# Sheet.net
KiCad netlist of a schematic drawn in Altium Designer
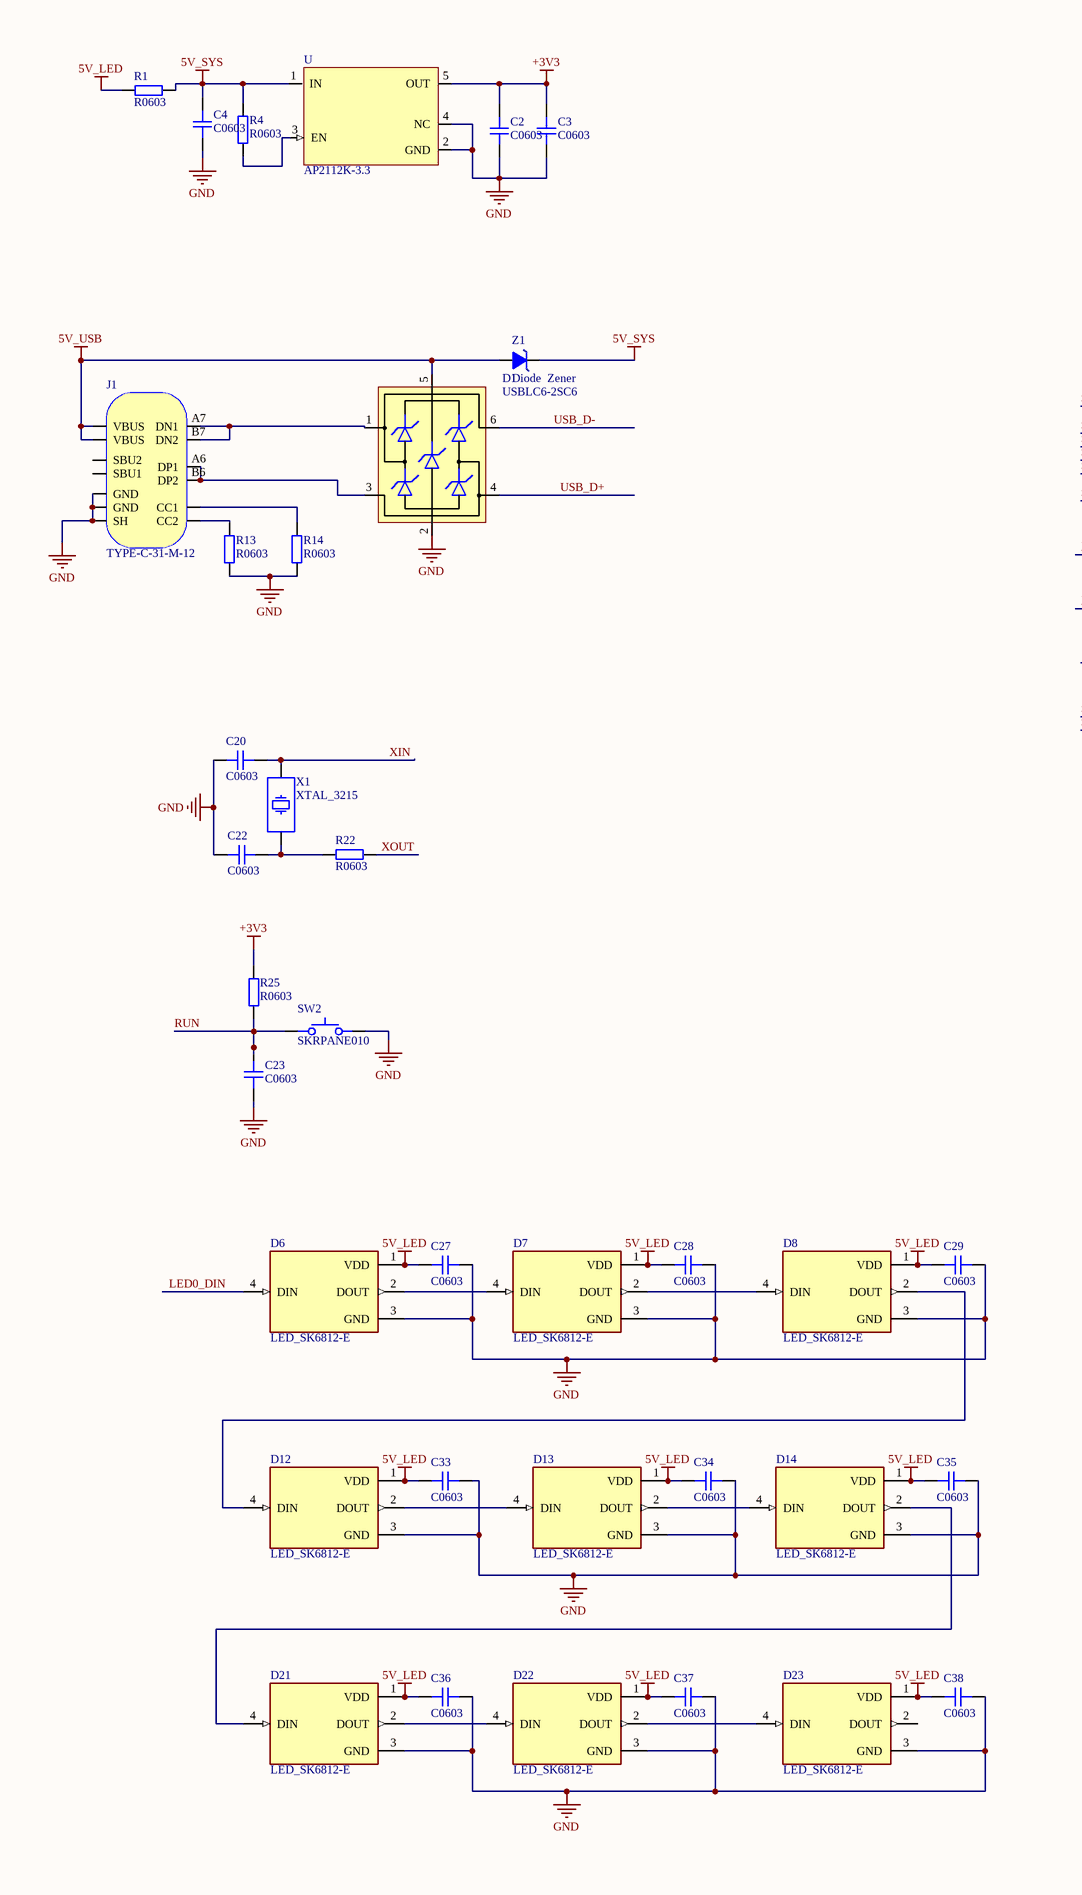
[diagram p0: Sheet.SchDoc, left]
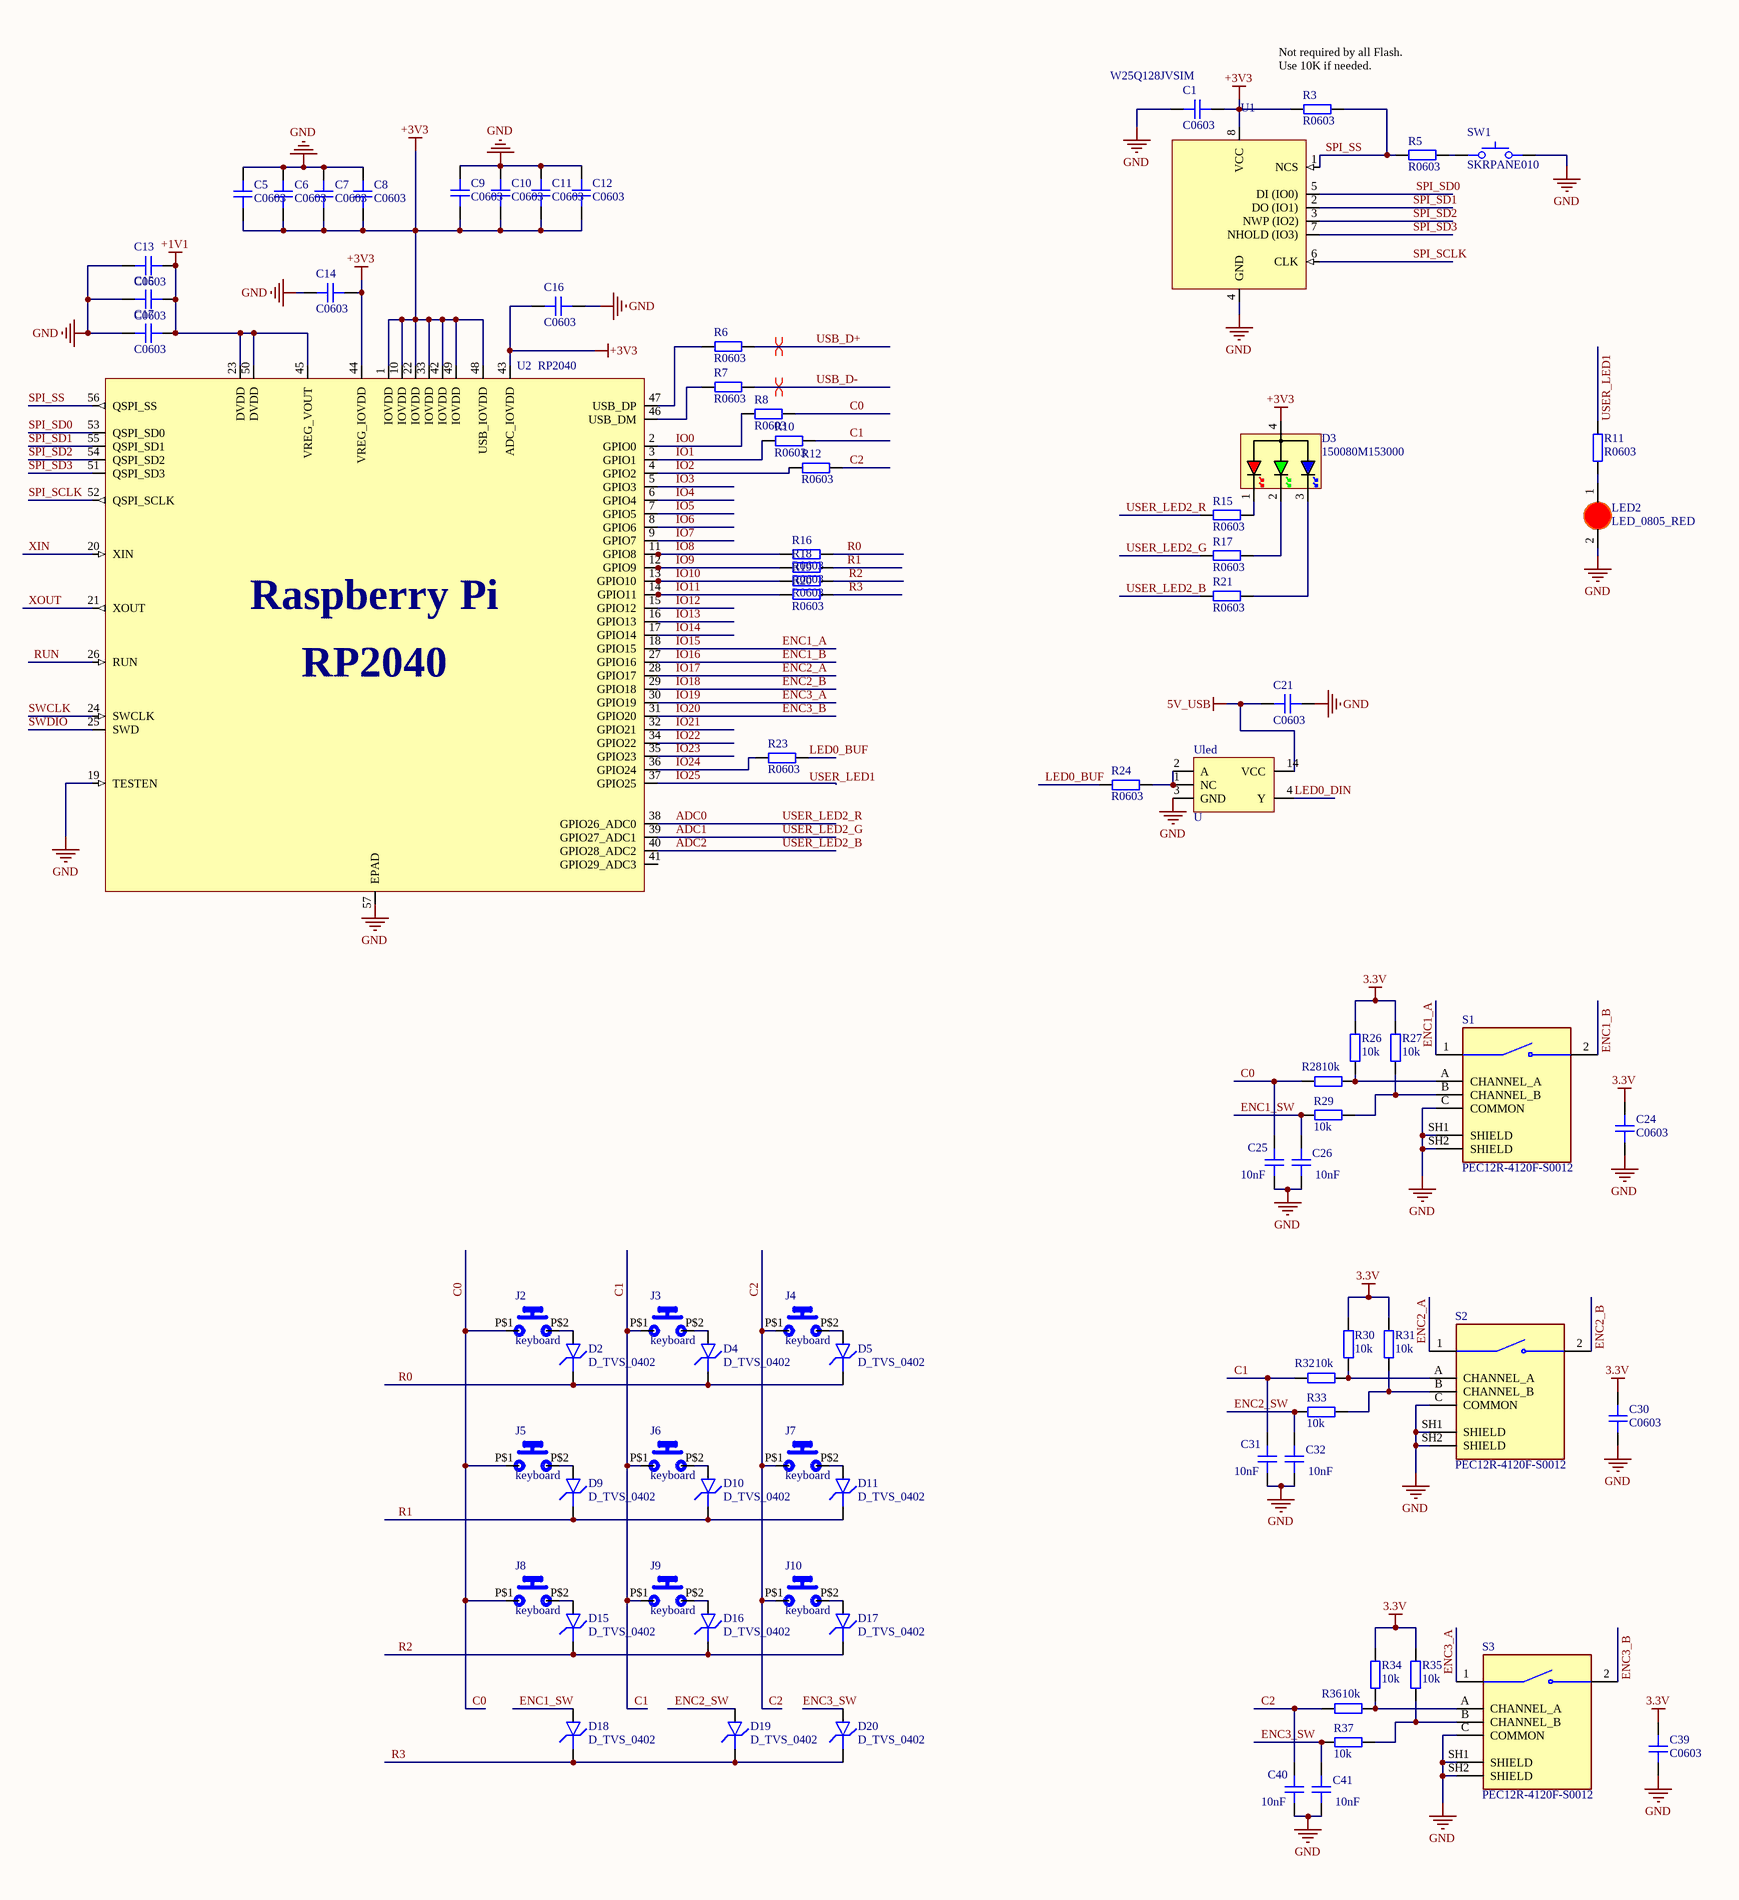
[diagram p1: Sheet.SchDoc, right]

(export (version "E")
  (design (tool "Eeschema 10.0.6"))
  (components
    (comp (ref "C1")
      (value "C0603")
      (footprint "CAP_0603")
      (description "Capacitor SMD 0603")
      (libsource (lib "bethu") (part "CAP_0603"))
    )
    (comp (ref "C2")
      (value "C0603")
      (footprint "CAP_0603")
      (description "Capacitor SMD 0603")
      (libsource (lib "bethu") (part "CAP_0603"))
    )
    (comp (ref "C3")
      (value "C0603")
      (footprint "CAP_0603")
      (description "Capacitor SMD 0603")
      (libsource (lib "bethu") (part "CAP_0603"))
    )
    (comp (ref "C4")
      (value "C0603")
      (footprint "CAP_0603")
      (description "Capacitor SMD 0603")
      (libsource (lib "bethu") (part "CAP_0603"))
    )
    (comp (ref "C5")
      (value "C0603")
      (footprint "CAP_0603")
      (description "Capacitor SMD 0603")
      (libsource (lib "bethu") (part "CAP_0603"))
    )
    (comp (ref "C6")
      (value "C0603")
      (footprint "CAP_0603")
      (description "Capacitor SMD 0603")
      (libsource (lib "bethu") (part "CAP_0603"))
    )
    (comp (ref "C7")
      (value "C0603")
      (footprint "CAP_0603")
      (description "Capacitor SMD 0603")
      (libsource (lib "bethu") (part "CAP_0603"))
    )
    (comp (ref "C8")
      (value "C0603")
      (footprint "CAP_0603")
      (description "Capacitor SMD 0603")
      (libsource (lib "bethu") (part "CAP_0603"))
    )
    (comp (ref "C9")
      (value "C0603")
      (footprint "CAP_0603")
      (description "Capacitor SMD 0603")
      (libsource (lib "bethu") (part "CAP_0603"))
    )
    (comp (ref "C10")
      (value "C0603")
      (footprint "CAP_0603")
      (description "Capacitor SMD 0603")
      (libsource (lib "bethu") (part "CAP_0603"))
    )
    (comp (ref "C11")
      (value "C0603")
      (footprint "CAP_0603")
      (description "Capacitor SMD 0603")
      (libsource (lib "bethu") (part "CAP_0603"))
    )
    (comp (ref "C12")
      (value "C0603")
      (footprint "CAP_0603")
      (description "Capacitor SMD 0603")
      (libsource (lib "bethu") (part "CAP_0603"))
    )
    (comp (ref "C13")
      (value "C0603")
      (footprint "CAP_0603")
      (description "Capacitor SMD 0603")
      (libsource (lib "bethu") (part "CAP_0603"))
    )
    (comp (ref "C14")
      (value "C0603")
      (footprint "CAP_0603")
      (description "Capacitor SMD 0603")
      (libsource (lib "bethu") (part "CAP_0603"))
    )
    (comp (ref "C15")
      (value "C0603")
      (footprint "CAP_0603")
      (description "Capacitor SMD 0603")
      (libsource (lib "bethu") (part "CAP_0603"))
    )
    (comp (ref "C16")
      (value "C0603")
      (footprint "CAP_0603")
      (description "Capacitor SMD 0603")
      (libsource (lib "bethu") (part "CAP_0603"))
    )
    (comp (ref "C17")
      (value "C0603")
      (footprint "CAP_0603")
      (description "Capacitor SMD 0603")
      (libsource (lib "bethu") (part "CAP_0603"))
    )
    (comp (ref "C20")
      (value "C0603")
      (footprint "CAP_0603")
      (description "Capacitor SMD 0603")
      (libsource (lib "bethu") (part "CAP_0603"))
    )
    (comp (ref "C21")
      (value "C0603")
      (footprint "CAP_0603")
      (description "Capacitor SMD 0603")
      (libsource (lib "bethu") (part "CAP_0603"))
    )
    (comp (ref "C22")
      (value "C0603")
      (footprint "CAP_0603")
      (description "Capacitor SMD 0603")
      (libsource (lib "bethu") (part "CAP_0603"))
    )
    (comp (ref "C23")
      (value "C0603")
      (footprint "CAP_0603")
      (description "Capacitor SMD 0603")
      (libsource (lib "bethu") (part "CAP_0603"))
    )
    (comp (ref "C24")
      (value "C0603")
      (footprint "CAP_0603")
      (description "Capacitor SMD 0603")
      (libsource (lib "bethu") (part "CAP_0603"))
    )
    (comp (ref "C25")
      (value "10nF")
      (footprint "CAP_0603")
      (description "Capacitor SMD 0603")
      (libsource (lib "bethu") (part "CAP_0603"))
    )
    (comp (ref "C26")
      (value "10nF")
      (footprint "CAP_0603")
      (description "Capacitor SMD 0603")
      (libsource (lib "bethu") (part "CAP_0603"))
    )
    (comp (ref "C27")
      (value "C0603")
      (footprint "CAP_0603")
      (description "Capacitor SMD 0603")
      (libsource (lib "bethu") (part "CAP_0603"))
    )
    (comp (ref "C28")
      (value "C0603")
      (footprint "CAP_0603")
      (description "Capacitor SMD 0603")
      (libsource (lib "bethu") (part "CAP_0603"))
    )
    (comp (ref "C29")
      (value "C0603")
      (footprint "CAP_0603")
      (description "Capacitor SMD 0603")
      (libsource (lib "bethu") (part "CAP_0603"))
    )
    (comp (ref "C30")
      (value "C0603")
      (footprint "CAP_0603")
      (description "Capacitor SMD 0603")
      (libsource (lib "bethu") (part "CAP_0603"))
    )
    (comp (ref "C31")
      (value "10nF")
      (footprint "CAP_0603")
      (description "Capacitor SMD 0603")
      (libsource (lib "bethu") (part "CAP_0603"))
    )
    (comp (ref "C32")
      (value "10nF")
      (footprint "CAP_0603")
      (description "Capacitor SMD 0603")
      (libsource (lib "bethu") (part "CAP_0603"))
    )
    (comp (ref "C33")
      (value "C0603")
      (footprint "CAP_0603")
      (description "Capacitor SMD 0603")
      (libsource (lib "bethu") (part "CAP_0603"))
    )
    (comp (ref "C34")
      (value "C0603")
      (footprint "CAP_0603")
      (description "Capacitor SMD 0603")
      (libsource (lib "bethu") (part "CAP_0603"))
    )
    (comp (ref "C35")
      (value "C0603")
      (footprint "CAP_0603")
      (description "Capacitor SMD 0603")
      (libsource (lib "bethu") (part "CAP_0603"))
    )
    (comp (ref "C36")
      (value "C0603")
      (footprint "CAP_0603")
      (description "Capacitor SMD 0603")
      (libsource (lib "bethu") (part "CAP_0603"))
    )
    (comp (ref "C37")
      (value "C0603")
      (footprint "CAP_0603")
      (description "Capacitor SMD 0603")
      (libsource (lib "bethu") (part "CAP_0603"))
    )
    (comp (ref "C38")
      (value "C0603")
      (footprint "CAP_0603")
      (description "Capacitor SMD 0603")
      (libsource (lib "bethu") (part "CAP_0603"))
    )
    (comp (ref "C39")
      (value "C0603")
      (footprint "CAP_0603")
      (description "Capacitor SMD 0603")
      (libsource (lib "bethu") (part "CAP_0603"))
    )
    (comp (ref "C40")
      (value "10nF")
      (footprint "CAP_0603")
      (description "Capacitor SMD 0603")
      (libsource (lib "bethu") (part "CAP_0603"))
    )
    (comp (ref "C41")
      (value "10nF")
      (footprint "CAP_0603")
      (description "Capacitor SMD 0603")
      (libsource (lib "bethu") (part "CAP_0603"))
    )
    (comp (ref "D1")
      (value "USBLC6-2SC6")
      (footprint "SOT-23-6")
      (description "Low-Capacitance ESD Protection USB")
      (fields (field (name "MANUFACTURER") "STMicroelectronics"))
      (libsource (lib "bethu") (part "USBLC6-2SC6"))
    )
    (comp (ref "D2")
      (value "D_TVS_0402")
      (footprint "D_0402")
      (description "Diode TVS / ESD 0402")
      (libsource (lib "bethu") (part "D_TVS_0402"))
    )
    (comp (ref "D3")
      (value "150080M153000")
      (footprint "150080M153000")
      (description "RGB LED Common Anode SMD Diffused 0805 Top View")
      (fields (field (name "MANUFACTURER") "Wurth"))
      (libsource (lib "bethu") (part "LED RGB"))
    )
    (comp (ref "D4")
      (value "D_TVS_0402")
      (footprint "D_0402")
      (description "Diode TVS / ESD 0402")
      (libsource (lib "bethu") (part "D_TVS_0402"))
    )
    (comp (ref "D5")
      (value "D_TVS_0402")
      (footprint "D_0402")
      (description "Diode TVS / ESD 0402")
      (libsource (lib "bethu") (part "D_TVS_0402"))
    )
    (comp (ref "D6")
      (value "LED_SK6812-E")
      (footprint "LED_SK6812-E")
      (fields (field (name "MF") "DONGGUANG OPSCO OPTOELECTRONICS CO., LTD") (field (name "MP") "SK6812-E"))
      (libsource (lib "bethu") (part "LED_SK6812-E"))
    )
    (comp (ref "D7")
      (value "LED_SK6812-E")
      (footprint "LED_SK6812-E")
      (fields (field (name "MF") "DONGGUANG OPSCO OPTOELECTRONICS CO., LTD") (field (name "MP") "SK6812-E"))
      (libsource (lib "bethu") (part "LED_SK6812-E"))
    )
    (comp (ref "D8")
      (value "LED_SK6812-E")
      (footprint "LED_SK6812-E")
      (fields (field (name "MF") "DONGGUANG OPSCO OPTOELECTRONICS CO., LTD") (field (name "MP") "SK6812-E"))
      (libsource (lib "bethu") (part "LED_SK6812-E"))
    )
    (comp (ref "D9")
      (value "D_TVS_0402")
      (footprint "D_0402")
      (description "Diode TVS / ESD 0402")
      (libsource (lib "bethu") (part "D_TVS_0402"))
    )
    (comp (ref "D10")
      (value "D_TVS_0402")
      (footprint "D_0402")
      (description "Diode TVS / ESD 0402")
      (libsource (lib "bethu") (part "D_TVS_0402"))
    )
    (comp (ref "D11")
      (value "D_TVS_0402")
      (footprint "D_0402")
      (description "Diode TVS / ESD 0402")
      (libsource (lib "bethu") (part "D_TVS_0402"))
    )
    (comp (ref "D12")
      (value "LED_SK6812-E")
      (footprint "LED_SK6812-E")
      (fields (field (name "MF") "DONGGUANG OPSCO OPTOELECTRONICS CO., LTD") (field (name "MP") "SK6812-E"))
      (libsource (lib "bethu") (part "LED_SK6812-E"))
    )
    (comp (ref "D13")
      (value "LED_SK6812-E")
      (footprint "LED_SK6812-E")
      (fields (field (name "MF") "DONGGUANG OPSCO OPTOELECTRONICS CO., LTD") (field (name "MP") "SK6812-E"))
      (libsource (lib "bethu") (part "LED_SK6812-E"))
    )
    (comp (ref "D14")
      (value "LED_SK6812-E")
      (footprint "LED_SK6812-E")
      (fields (field (name "MF") "DONGGUANG OPSCO OPTOELECTRONICS CO., LTD") (field (name "MP") "SK6812-E"))
      (libsource (lib "bethu") (part "LED_SK6812-E"))
    )
    (comp (ref "D15")
      (value "D_TVS_0402")
      (footprint "D_0402")
      (description "Diode TVS / ESD 0402")
      (libsource (lib "bethu") (part "D_TVS_0402"))
    )
    (comp (ref "D16")
      (value "D_TVS_0402")
      (footprint "D_0402")
      (description "Diode TVS / ESD 0402")
      (libsource (lib "bethu") (part "D_TVS_0402"))
    )
    (comp (ref "D17")
      (value "D_TVS_0402")
      (footprint "D_0402")
      (description "Diode TVS / ESD 0402")
      (libsource (lib "bethu") (part "D_TVS_0402"))
    )
    (comp (ref "D18")
      (value "D_TVS_0402")
      (footprint "D_0402")
      (description "Diode TVS / ESD 0402")
      (libsource (lib "bethu") (part "D_TVS_0402"))
    )
    (comp (ref "D19")
      (value "D_TVS_0402")
      (footprint "D_0402")
      (description "Diode TVS / ESD 0402")
      (libsource (lib "bethu") (part "D_TVS_0402"))
    )
    (comp (ref "D20")
      (value "D_TVS_0402")
      (footprint "D_0402")
      (description "Diode TVS / ESD 0402")
      (libsource (lib "bethu") (part "D_TVS_0402"))
    )
    (comp (ref "D21")
      (value "LED_SK6812-E")
      (footprint "LED_SK6812-E")
      (fields (field (name "MF") "DONGGUANG OPSCO OPTOELECTRONICS CO., LTD") (field (name "MP") "SK6812-E"))
      (libsource (lib "bethu") (part "LED_SK6812-E"))
    )
    (comp (ref "D22")
      (value "LED_SK6812-E")
      (footprint "LED_SK6812-E")
      (fields (field (name "MF") "DONGGUANG OPSCO OPTOELECTRONICS CO., LTD") (field (name "MP") "SK6812-E"))
      (libsource (lib "bethu") (part "LED_SK6812-E"))
    )
    (comp (ref "D23")
      (value "LED_SK6812-E")
      (footprint "LED_SK6812-E")
      (fields (field (name "MF") "DONGGUANG OPSCO OPTOELECTRONICS CO., LTD") (field (name "MP") "SK6812-E"))
      (libsource (lib "bethu") (part "LED_SK6812-E"))
    )
    (comp (ref "J1")
      (value "TYPE-C-31-M-12")
      (footprint "TYPE-C-31-M-12")
      (description "USB Type C Connector Horizontal SMT")
      (fields (field (name "MANUFACTURER") "Koren Hroparts"))
      (libsource (lib "bethu") (part "TYPE-C-31-M-12"))
    )
    (comp (ref "J2")
      (value "keyboard")
      (footprint "SWITCH_keyboard")
      (fields (field (name "MF") "Cherry") (field (name "MP") "MX1A-11NN"))
      (libsource (lib "bethu") (part "keyboard"))
    )
    (comp (ref "J3")
      (value "keyboard")
      (footprint "SWITCH_keyboard")
      (fields (field (name "MF") "Cherry") (field (name "MP") "MX1A-11NN"))
      (libsource (lib "bethu") (part "keyboard"))
    )
    (comp (ref "J4")
      (value "keyboard")
      (footprint "SWITCH_keyboard")
      (fields (field (name "MF") "Cherry") (field (name "MP") "MX1A-11NN"))
      (libsource (lib "bethu") (part "keyboard"))
    )
    (comp (ref "J5")
      (value "keyboard")
      (footprint "SWITCH_keyboard")
      (fields (field (name "MF") "Cherry") (field (name "MP") "MX1A-11NN"))
      (libsource (lib "bethu") (part "keyboard"))
    )
    (comp (ref "J6")
      (value "keyboard")
      (footprint "SWITCH_keyboard")
      (fields (field (name "MF") "Cherry") (field (name "MP") "MX1A-11NN"))
      (libsource (lib "bethu") (part "keyboard"))
    )
    (comp (ref "J7")
      (value "keyboard")
      (footprint "SWITCH_keyboard")
      (fields (field (name "MF") "Cherry") (field (name "MP") "MX1A-11NN"))
      (libsource (lib "bethu") (part "keyboard"))
    )
    (comp (ref "J8")
      (value "keyboard")
      (footprint "SWITCH_keyboard")
      (fields (field (name "MF") "Cherry") (field (name "MP") "MX1A-11NN"))
      (libsource (lib "bethu") (part "keyboard"))
    )
    (comp (ref "J9")
      (value "keyboard")
      (footprint "SWITCH_keyboard")
      (fields (field (name "MF") "Cherry") (field (name "MP") "MX1A-11NN"))
      (libsource (lib "bethu") (part "keyboard"))
    )
    (comp (ref "J10")
      (value "keyboard")
      (footprint "SWITCH_keyboard")
      (fields (field (name "MF") "Cherry") (field (name "MP") "MX1A-11NN"))
      (libsource (lib "bethu") (part "keyboard"))
    )
    (comp (ref "LED2")
      (value "LED_0805_RED")
      (footprint "LED-0805-Red")
      (libsource (lib "bethu") (part "LED_0805_RED"))
    )
    (comp (ref "R1")
      (value "R0603")
      (footprint "RES_0603")
      (description "Resistor SMD 0603")
      (libsource (lib "bethu") (part "RES_0603"))
    )
    (comp (ref "R3")
      (value "R0603")
      (footprint "RES_0603")
      (description "Resistor SMD 0603")
      (libsource (lib "bethu") (part "RES_0603"))
    )
    (comp (ref "R4")
      (value "R0603")
      (footprint "RES_0603")
      (description "Resistor SMD 0603")
      (libsource (lib "bethu") (part "RES_0603"))
    )
    (comp (ref "R5")
      (value "R0603")
      (footprint "RES_0603")
      (description "Resistor SMD 0603")
      (libsource (lib "bethu") (part "RES_0603"))
    )
    (comp (ref "R6")
      (value "R0603")
      (footprint "RES_0603")
      (description "Resistor SMD 0603")
      (libsource (lib "bethu") (part "RES_0603"))
    )
    (comp (ref "R7")
      (value "R0603")
      (footprint "RES_0603")
      (description "Resistor SMD 0603")
      (libsource (lib "bethu") (part "RES_0603"))
    )
    (comp (ref "R8")
      (value "R0603")
      (footprint "RES_0603")
      (description "Resistor SMD 0603")
      (libsource (lib "bethu") (part "RES_0603"))
    )
    (comp (ref "R10")
      (value "R0603")
      (footprint "RES_0603")
      (description "Resistor SMD 0603")
      (libsource (lib "bethu") (part "RES_0603"))
    )
    (comp (ref "R11")
      (value "R0603")
      (footprint "RES_0603")
      (description "Resistor SMD 0603")
      (libsource (lib "bethu") (part "RES_0603"))
    )
    (comp (ref "R12")
      (value "R0603")
      (footprint "RES_0603")
      (description "Resistor SMD 0603")
      (libsource (lib "bethu") (part "RES_0603"))
    )
    (comp (ref "R13")
      (value "R0603")
      (footprint "RES_0603")
      (description "Resistor SMD 0603")
      (libsource (lib "bethu") (part "RES_0603"))
    )
    (comp (ref "R14")
      (value "R0603")
      (footprint "RES_0603")
      (description "Resistor SMD 0603")
      (libsource (lib "bethu") (part "RES_0603"))
    )
    (comp (ref "R15")
      (value "R0603")
      (footprint "RES_0603")
      (description "Resistor SMD 0603")
      (libsource (lib "bethu") (part "RES_0603"))
    )
    (comp (ref "R16")
      (value "R0603")
      (footprint "RES_0603")
      (description "Resistor SMD 0603")
      (libsource (lib "bethu") (part "RES_0603"))
    )
    (comp (ref "R17")
      (value "R0603")
      (footprint "RES_0603")
      (description "Resistor SMD 0603")
      (libsource (lib "bethu") (part "RES_0603"))
    )
    (comp (ref "R18")
      (value "R0603")
      (footprint "RES_0603")
      (description "Resistor SMD 0603")
      (libsource (lib "bethu") (part "RES_0603"))
    )
    (comp (ref "R19")
      (value "R0603")
      (footprint "RES_0603")
      (description "Resistor SMD 0603")
      (libsource (lib "bethu") (part "RES_0603"))
    )
    (comp (ref "R20")
      (value "R0603")
      (footprint "RES_0603")
      (description "Resistor SMD 0603")
      (libsource (lib "bethu") (part "RES_0603"))
    )
    (comp (ref "R21")
      (value "R0603")
      (footprint "RES_0603")
      (description "Resistor SMD 0603")
      (libsource (lib "bethu") (part "RES_0603"))
    )
    (comp (ref "R22")
      (value "R0603")
      (footprint "RES_0603")
      (description "Resistor SMD 0603")
      (libsource (lib "bethu") (part "RES_0603"))
    )
    (comp (ref "R23")
      (value "R0603")
      (footprint "RES_0603")
      (description "Resistor SMD 0603")
      (libsource (lib "bethu") (part "RES_0603"))
    )
    (comp (ref "R24")
      (value "R0603")
      (footprint "RES_0603")
      (description "Resistor SMD 0603")
      (libsource (lib "bethu") (part "RES_0603"))
    )
    (comp (ref "R25")
      (value "R0603")
      (footprint "RES_0603")
      (description "Resistor SMD 0603")
      (libsource (lib "bethu") (part "RES_0603"))
    )
    (comp (ref "R26")
      (value "10k")
      (footprint "RES_0603")
      (description "Resistor SMD 0603")
      (libsource (lib "bethu") (part "RES_0603"))
    )
    (comp (ref "R27")
      (value "10k")
      (footprint "RES_0603")
      (description "Resistor SMD 0603")
      (libsource (lib "bethu") (part "RES_0603"))
    )
    (comp (ref "R28")
      (value "10k")
      (footprint "RES_0603")
      (description "Resistor SMD 0603")
      (libsource (lib "bethu") (part "RES_0603"))
    )
    (comp (ref "R29")
      (value "10k")
      (footprint "RES_0603")
      (description "Resistor SMD 0603")
      (libsource (lib "bethu") (part "RES_0603"))
    )
    (comp (ref "R30")
      (value "10k")
      (footprint "RES_0603")
      (description "Resistor SMD 0603")
      (libsource (lib "bethu") (part "RES_0603"))
    )
    (comp (ref "R31")
      (value "10k")
      (footprint "RES_0603")
      (description "Resistor SMD 0603")
      (libsource (lib "bethu") (part "RES_0603"))
    )
    (comp (ref "R32")
      (value "10k")
      (footprint "RES_0603")
      (description "Resistor SMD 0603")
      (libsource (lib "bethu") (part "RES_0603"))
    )
    (comp (ref "R33")
      (value "10k")
      (footprint "RES_0603")
      (description "Resistor SMD 0603")
      (libsource (lib "bethu") (part "RES_0603"))
    )
    (comp (ref "R34")
      (value "10k")
      (footprint "RES_0603")
      (description "Resistor SMD 0603")
      (libsource (lib "bethu") (part "RES_0603"))
    )
    (comp (ref "R35")
      (value "10k")
      (footprint "RES_0603")
      (description "Resistor SMD 0603")
      (libsource (lib "bethu") (part "RES_0603"))
    )
    (comp (ref "R36")
      (value "10k")
      (footprint "RES_0603")
      (description "Resistor SMD 0603")
      (libsource (lib "bethu") (part "RES_0603"))
    )
    (comp (ref "R37")
      (value "10k")
      (footprint "RES_0603")
      (description "Resistor SMD 0603")
      (libsource (lib "bethu") (part "RES_0603"))
    )
    (comp (ref "S1")
      (value "PEC12R-4120F-S0012")
      (footprint "XDCR_PEC12R-4120F-S0012")
      (fields (field (name "MF") "Bourns Inc."))
      (libsource (lib "bethu") (part "PEC12R-4120F-S0012"))
    )
    (comp (ref "S2")
      (value "PEC12R-4120F-S0012")
      (footprint "XDCR_PEC12R-4120F-S0012")
      (fields (field (name "MF") "Bourns Inc."))
      (libsource (lib "bethu") (part "PEC12R-4120F-S0012"))
    )
    (comp (ref "S3")
      (value "PEC12R-4120F-S0012")
      (footprint "XDCR_PEC12R-4120F-S0012")
      (fields (field (name "MF") "Bourns Inc."))
      (libsource (lib "bethu") (part "PEC12R-4120F-S0012"))
    )
    (comp (ref "SW1")
      (value "SKRPANE010")
      (footprint "SKRPANE010")
      (description "Tactile Switch SMD SPST")
      (fields (field (name "MANUFACTURER") "Alps Alpine"))
      (libsource (lib "bethu") (part "SKRPANE010"))
    )
    (comp (ref "SW2")
      (value "SKRPANE010")
      (footprint "SKRPANE010")
      (description "Tactile Switch SMD SPST")
      (fields (field (name "MANUFACTURER") "Alps Alpine"))
      (libsource (lib "bethu") (part "SKRPANE010"))
    )
    (comp (ref "U")
      (value "AP2112K-3.3")
      (footprint "SOT23 - 5 Leads")
      (libsource (lib "bethu") (part "AP2112K-3.3"))
    )
    (comp (ref "U1")
      (value "W25Q128JVSIM")
      (footprint "SOIC-8")
      (description "128M-BIT\r\nSERIAL FLASH MEMORY WITH\r\nDUAL/QUAD SPI & QPI & DTR SOIC-8")
      (fields (field (name "MANUFACTURER") "Winbond"))
      (libsource (lib "bethu") (part "W25Q128JVSIM"))
    )
    (comp (ref "U2")
      (value "RP2040")
      (footprint "QFN-56-EP")
      (description "32-Bit Dual-Core ARM Cortex-M0+ Microcontroller")
      (fields (field (name "MANUFACTURER") "Raspberry Pi"))
      (libsource (lib "bethu") (part "RP2040"))
    )
    (comp (ref "Uled")
      (value "U")
      (footprint "SOT23 - 5 Leads")
      (libsource (lib "bethu") (part "SN74LV1T34DBVR"))
    )
    (comp (ref "X1")
      (value "XTAL_3215")
      (footprint "XTAL_3215-2")
      (description "Crystal SMD 3215")
      (libsource (lib "bethu") (part "XTAL_3215"))
    )
    (comp (ref "Z1")
      (value "Diode  Zener")
      (footprint "DIODE SMA")
      (libsource (lib "bethu") (part "Diode Zener"))
    )
  )
  (nets
    (net (code "1") (name "+1V1") (class "Default")
      (node (ref "C13") (pin "1") (pinfunction "1_1") (pintype "passive"))
      (node (ref "C15") (pin "2") (pinfunction "2_2") (pintype "passive"))
      (node (ref "C17") (pin "2") (pinfunction "2_2") (pintype "passive"))
      (node (ref "U2") (pin "23") (pinfunction "DVDD_23") (pintype "power_in"))
      (node (ref "U2") (pin "45") (pinfunction "VREG_VOUT_45") (pintype "power_in"))
      (node (ref "U2") (pin "50") (pinfunction "DVDD_50") (pintype "power_in"))
    )
    (net (code "2") (name "+3V3") (class "Default")
      (node (ref "C1") (pin "2") (pinfunction "2_2") (pintype "passive"))
      (node (ref "C10") (pin "1") (pinfunction "1_1") (pintype "passive"))
      (node (ref "C11") (pin "1") (pinfunction "1_1") (pintype "passive"))
      (node (ref "C12") (pin "1") (pinfunction "1_1") (pintype "passive"))
      (node (ref "C14") (pin "1") (pinfunction "1_1") (pintype "passive"))
      (node (ref "C16") (pin "1") (pinfunction "1_1") (pintype "passive"))
      (node (ref "C2") (pin "2") (pinfunction "2_2") (pintype "passive"))
      (node (ref "C3") (pin "2") (pinfunction "2_2") (pintype "passive"))
      (node (ref "C5") (pin "1") (pinfunction "1_1") (pintype "passive"))
      (node (ref "C6") (pin "1") (pinfunction "1_1") (pintype "passive"))
      (node (ref "C7") (pin "1") (pinfunction "1_1") (pintype "passive"))
      (node (ref "C8") (pin "1") (pinfunction "1_1") (pintype "passive"))
      (node (ref "C9") (pin "1") (pinfunction "1_1") (pintype "passive"))
      (node (ref "D3") (pin "4") (pinfunction "AC_4") (pintype "passive"))
      (node (ref "R25") (pin "2") (pinfunction "2_2") (pintype "passive"))
      (node (ref "R3") (pin "1") (pinfunction "1_1") (pintype "passive"))
      (node (ref "U") (pin "5") (pinfunction "OUT_5") (pintype "power_in"))
      (node (ref "U1") (pin "8") (pinfunction "VCC_8") (pintype "power_in"))
      (node (ref "U2") (pin "1") (pinfunction "IOVDD_1") (pintype "power_in"))
      (node (ref "U2") (pin "10") (pinfunction "IOVDD_10") (pintype "power_in"))
      (node (ref "U2") (pin "22") (pinfunction "IOVDD_22") (pintype "power_in"))
      (node (ref "U2") (pin "33") (pinfunction "IOVDD_33") (pintype "power_in"))
      (node (ref "U2") (pin "42") (pinfunction "IOVDD_42") (pintype "power_in"))
      (node (ref "U2") (pin "43") (pinfunction "ADC_IOVDD_43") (pintype "power_in"))
      (node (ref "U2") (pin "44") (pinfunction "VREG_IOVDD_44") (pintype "power_in"))
      (node (ref "U2") (pin "48") (pinfunction "USB_IOVDD_48") (pintype "power_in"))
      (node (ref "U2") (pin "49") (pinfunction "IOVDD_49") (pintype "power_in"))
    )
    (net (code "3") (name "/ADC0") (class "Default")
      (node (ref "R15") (pin "1") (pinfunction "1_1") (pintype "passive"))
      (node (ref "U2") (pin "38") (pinfunction "GPIO26_ADC0_38") (pintype "bidirectional"))
    )
    (net (code "4") (name "/ADC1") (class "Default")
      (node (ref "R17") (pin "1") (pinfunction "1_1") (pintype "passive"))
      (node (ref "U2") (pin "39") (pinfunction "GPIO27_ADC1_39") (pintype "bidirectional"))
    )
    (net (code "5") (name "/ADC2") (class "Default")
      (node (ref "R21") (pin "1") (pinfunction "1_1") (pintype "passive"))
      (node (ref "U2") (pin "40") (pinfunction "GPIO28_ADC2_40") (pintype "bidirectional"))
    )
    (net (code "6") (name "/C0") (class "Default")
      (node (ref "C25") (pin "2") (pinfunction "2_2") (pintype "passive"))
      (node (ref "J2") (pin "P$1") (pinfunction "P_P$1") (pintype "passive"))
      (node (ref "J5") (pin "P$1") (pinfunction "P_P$1") (pintype "passive"))
      (node (ref "J8") (pin "P$1") (pinfunction "P_P$1") (pintype "passive"))
      (node (ref "R28") (pin "2") (pinfunction "2_2") (pintype "passive"))
      (node (ref "R8") (pin "2") (pinfunction "2_2") (pintype "passive"))
    )
    (net (code "7") (name "/C1") (class "Default")
      (node (ref "C31") (pin "2") (pinfunction "2_2") (pintype "passive"))
      (node (ref "J3") (pin "P$1") (pinfunction "P_P$1") (pintype "passive"))
      (node (ref "J6") (pin "P$1") (pinfunction "P_P$1") (pintype "passive"))
      (node (ref "J9") (pin "P$1") (pinfunction "P_P$1") (pintype "passive"))
      (node (ref "R10") (pin "2") (pinfunction "2_2") (pintype "passive"))
      (node (ref "R32") (pin "2") (pinfunction "2_2") (pintype "passive"))
    )
    (net (code "8") (name "/C2") (class "Default")
      (node (ref "C40") (pin "2") (pinfunction "2_2") (pintype "passive"))
      (node (ref "J10") (pin "P$1") (pinfunction "P_P$1") (pintype "passive"))
      (node (ref "J4") (pin "P$1") (pinfunction "P_P$1") (pintype "passive"))
      (node (ref "J7") (pin "P$1") (pinfunction "P_P$1") (pintype "passive"))
      (node (ref "R12") (pin "2") (pinfunction "2_2") (pintype "passive"))
      (node (ref "R36") (pin "2") (pinfunction "2_2") (pintype "passive"))
    )
    (net (code "9") (name "/ENC1_A") (class "Default")
      (node (ref "S1") (pin "1") (pinfunction "1_1") (pintype "passive"))
      (node (ref "U2") (pin "18") (pinfunction "GPIO15_18") (pintype "bidirectional"))
    )
    (net (code "10") (name "/ENC1_B") (class "Default")
      (node (ref "S1") (pin "2") (pinfunction "2_2") (pintype "passive"))
      (node (ref "U2") (pin "27") (pinfunction "GPIO16_27") (pintype "bidirectional"))
    )
    (net (code "11") (name "/ENC1_SW") (class "Default")
      (node (ref "C26") (pin "2") (pinfunction "2_2") (pintype "passive"))
      (node (ref "D18") (pin "A") (pinfunction "A_A") (pintype "passive"))
      (node (ref "R29") (pin "2") (pinfunction "2_2") (pintype "passive"))
    )
    (net (code "12") (name "/ENC2_A") (class "Default")
      (node (ref "S2") (pin "1") (pinfunction "1_1") (pintype "passive"))
      (node (ref "U2") (pin "28") (pinfunction "GPIO17_28") (pintype "bidirectional"))
    )
    (net (code "13") (name "/ENC2_B") (class "Default")
      (node (ref "S2") (pin "2") (pinfunction "2_2") (pintype "passive"))
      (node (ref "U2") (pin "29") (pinfunction "GPIO18_29") (pintype "bidirectional"))
    )
    (net (code "14") (name "/ENC2_SW") (class "Default")
      (node (ref "C32") (pin "2") (pinfunction "2_2") (pintype "passive"))
      (node (ref "D19") (pin "A") (pinfunction "A_A") (pintype "passive"))
      (node (ref "R33") (pin "2") (pinfunction "2_2") (pintype "passive"))
    )
    (net (code "15") (name "/ENC3_A") (class "Default")
      (node (ref "S3") (pin "1") (pinfunction "1_1") (pintype "passive"))
      (node (ref "U2") (pin "30") (pinfunction "GPIO19_30") (pintype "bidirectional"))
    )
    (net (code "16") (name "/ENC3_B") (class "Default")
      (node (ref "S3") (pin "2") (pinfunction "2_2") (pintype "passive"))
      (node (ref "U2") (pin "31") (pinfunction "GPIO20_31") (pintype "bidirectional"))
    )
    (net (code "17") (name "/ENC3_SW") (class "Default")
      (node (ref "C41") (pin "2") (pinfunction "2_2") (pintype "passive"))
      (node (ref "D20") (pin "A") (pinfunction "A_A") (pintype "passive"))
      (node (ref "R37") (pin "2") (pinfunction "2_2") (pintype "passive"))
    )
    (net (code "18") (name "/IO0") (class "Default")
      (node (ref "R8") (pin "1") (pinfunction "1_1") (pintype "passive"))
      (node (ref "U2") (pin "2") (pinfunction "GPIO0_2") (pintype "bidirectional"))
    )
    (net (code "19") (name "/IO1") (class "Default")
      (node (ref "R10") (pin "1") (pinfunction "1_1") (pintype "passive"))
      (node (ref "U2") (pin "3") (pinfunction "GPIO1_3") (pintype "bidirectional"))
    )
    (net (code "20") (name "/IO2") (class "Default")
      (node (ref "R12") (pin "1") (pinfunction "1_1") (pintype "passive"))
      (node (ref "U2") (pin "4") (pinfunction "GPIO2_4") (pintype "bidirectional"))
    )
    (net (code "21") (name "/IO3") (class "Default")
      (node (ref "U2") (pin "5") (pinfunction "GPIO3_5") (pintype "bidirectional"))
    )
    (net (code "22") (name "/IO4") (class "Default")
      (node (ref "U2") (pin "6") (pinfunction "GPIO4_6") (pintype "bidirectional"))
    )
    (net (code "23") (name "/IO5") (class "Default")
      (node (ref "U2") (pin "7") (pinfunction "GPIO5_7") (pintype "bidirectional"))
    )
    (net (code "24") (name "/IO6") (class "Default")
      (node (ref "U2") (pin "8") (pinfunction "GPIO6_8") (pintype "bidirectional"))
    )
    (net (code "25") (name "/IO7") (class "Default")
      (node (ref "U2") (pin "9") (pinfunction "GPIO7_9") (pintype "bidirectional"))
    )
    (net (code "26") (name "/IO8") (class "Default")
      (node (ref "R16") (pin "1") (pinfunction "1_1") (pintype "passive"))
      (node (ref "U2") (pin "11") (pinfunction "GPIO8_11") (pintype "bidirectional"))
    )
    (net (code "27") (name "/IO9") (class "Default")
      (node (ref "R18") (pin "1") (pinfunction "1_1") (pintype "passive"))
      (node (ref "U2") (pin "12") (pinfunction "GPIO9_12") (pintype "bidirectional"))
    )
    (net (code "28") (name "/IO10") (class "Default")
      (node (ref "R19") (pin "1") (pinfunction "1_1") (pintype "passive"))
      (node (ref "U2") (pin "13") (pinfunction "GPIO10_13") (pintype "bidirectional"))
    )
    (net (code "29") (name "/IO11") (class "Default")
      (node (ref "R20") (pin "1") (pinfunction "1_1") (pintype "passive"))
      (node (ref "U2") (pin "14") (pinfunction "GPIO11_14") (pintype "bidirectional"))
    )
    (net (code "30") (name "/IO12") (class "Default")
      (node (ref "U2") (pin "15") (pinfunction "GPIO12_15") (pintype "bidirectional"))
    )
    (net (code "31") (name "/IO13") (class "Default")
      (node (ref "U2") (pin "16") (pinfunction "GPIO13_16") (pintype "bidirectional"))
    )
    (net (code "32") (name "/IO14") (class "Default")
      (node (ref "U2") (pin "17") (pinfunction "GPIO14_17") (pintype "bidirectional"))
    )
    (net (code "33") (name "/IO21") (class "Default")
      (node (ref "U2") (pin "32") (pinfunction "GPIO21_32") (pintype "bidirectional"))
    )
    (net (code "34") (name "/IO22") (class "Default")
      (node (ref "U2") (pin "34") (pinfunction "GPIO22_34") (pintype "bidirectional"))
    )
    (net (code "35") (name "/IO23") (class "Default")
      (node (ref "U2") (pin "35") (pinfunction "GPIO23_35") (pintype "bidirectional"))
    )
    (net (code "36") (name "/IO24") (class "Default")
      (node (ref "R23") (pin "1") (pinfunction "1_1") (pintype "passive"))
      (node (ref "U2") (pin "36") (pinfunction "GPIO24_36") (pintype "bidirectional"))
    )
    (net (code "37") (name "/IO25") (class "Default")
      (node (ref "U2") (pin "37") (pinfunction "GPIO25_37") (pintype "bidirectional"))
    )
    (net (code "38") (name "/LED0_BUF") (class "Default")
      (node (ref "R23") (pin "2") (pinfunction "2_2") (pintype "passive"))
      (node (ref "R24") (pin "1") (pinfunction "1_1") (pintype "passive"))
    )
    (net (code "39") (name "/LED0_DIN") (class "Default")
      (node (ref "D6") (pin "4") (pinfunction "DIN_4") (pintype "input"))
      (node (ref "Uled") (pin "4") (pinfunction "Y_4") (pintype "passive"))
    )
    (net (code "40") (name "/R0") (class "Default")
      (node (ref "D2") (pin "K") (pinfunction "K_K") (pintype "passive"))
      (node (ref "D4") (pin "K") (pinfunction "K_K") (pintype "passive"))
      (node (ref "D5") (pin "K") (pinfunction "K_K") (pintype "passive"))
      (node (ref "R16") (pin "2") (pinfunction "2_2") (pintype "passive"))
    )
    (net (code "41") (name "/R1") (class "Default")
      (node (ref "D10") (pin "K") (pinfunction "K_K") (pintype "passive"))
      (node (ref "D11") (pin "K") (pinfunction "K_K") (pintype "passive"))
      (node (ref "D9") (pin "K") (pinfunction "K_K") (pintype "passive"))
      (node (ref "R18") (pin "2") (pinfunction "2_2") (pintype "passive"))
    )
    (net (code "42") (name "/R2") (class "Default")
      (node (ref "D15") (pin "K") (pinfunction "K_K") (pintype "passive"))
      (node (ref "D16") (pin "K") (pinfunction "K_K") (pintype "passive"))
      (node (ref "D17") (pin "K") (pinfunction "K_K") (pintype "passive"))
      (node (ref "R19") (pin "2") (pinfunction "2_2") (pintype "passive"))
    )
    (net (code "43") (name "/R3") (class "Default")
      (node (ref "D18") (pin "K") (pinfunction "K_K") (pintype "passive"))
      (node (ref "D19") (pin "K") (pinfunction "K_K") (pintype "passive"))
      (node (ref "D20") (pin "K") (pinfunction "K_K") (pintype "passive"))
      (node (ref "R20") (pin "2") (pinfunction "2_2") (pintype "passive"))
    )
    (net (code "44") (name "/RUN") (class "Default")
      (node (ref "C23") (pin "2") (pinfunction "2_2") (pintype "passive"))
      (node (ref "R25") (pin "1") (pinfunction "1_1") (pintype "passive"))
      (node (ref "SW2") (pin "12") (pintype "passive"))
      (node (ref "U2") (pin "26") (pinfunction "RUN_26") (pintype "input"))
    )
    (net (code "45") (name "/SPI_SCLK") (class "Default")
      (node (ref "U1") (pin "6") (pinfunction "CLK_6") (pintype "input"))
      (node (ref "U2") (pin "52") (pinfunction "QSPI_SCLK_52") (pintype "output"))
    )
    (net (code "46") (name "/SPI_SD0") (class "Default")
      (node (ref "U1") (pin "5") (pinfunction "DI_(IO0)_5") (pintype "bidirectional"))
      (node (ref "U2") (pin "53") (pinfunction "QSPI_SD0_53") (pintype "bidirectional"))
    )
    (net (code "47") (name "/SPI_SD1") (class "Default")
      (node (ref "U1") (pin "2") (pinfunction "DO_(IO1)_2") (pintype "bidirectional"))
      (node (ref "U2") (pin "55") (pinfunction "QSPI_SD1_55") (pintype "bidirectional"))
    )
    (net (code "48") (name "/SPI_SD2") (class "Default")
      (node (ref "U1") (pin "3") (pinfunction "NWP_(IO2)_3") (pintype "bidirectional"))
      (node (ref "U2") (pin "54") (pinfunction "QSPI_SD2_54") (pintype "bidirectional"))
    )
    (net (code "49") (name "/SPI_SD3") (class "Default")
      (node (ref "U1") (pin "7") (pinfunction "NHOLD_(IO3)_7") (pintype "bidirectional"))
      (node (ref "U2") (pin "51") (pinfunction "QSPI_SD3_51") (pintype "bidirectional"))
    )
    (net (code "50") (name "/SPI_SS") (class "Default")
      (node (ref "R3") (pin "2") (pinfunction "2_2") (pintype "passive"))
      (node (ref "R5") (pin "1") (pinfunction "1_1") (pintype "passive"))
      (node (ref "U1") (pin "1") (pinfunction "NCS_1") (pintype "input"))
      (node (ref "U2") (pin "56") (pinfunction "QSPI_SS_56") (pintype "output"))
    )
    (net (code "51") (name "/SWCLK") (class "Default")
      (node (ref "U2") (pin "24") (pinfunction "SWCLK_24") (pintype "input"))
    )
    (net (code "52") (name "/SWDIO") (class "Default")
      (node (ref "U2") (pin "25") (pinfunction "SWD_25") (pintype "bidirectional"))
    )
    (net (code "53") (name "/USB_D+") (class "Default")
      (node (ref "D1") (pin "4") (pinfunction "IO2_4") (pintype "bidirectional"))
      (node (ref "R6") (pin "2") (pinfunction "2_2") (pintype "passive"))
    )
    (net (code "54") (name "/USB_D-") (class "Default")
      (node (ref "D1") (pin "6") (pinfunction "IO1_6") (pintype "bidirectional"))
      (node (ref "R7") (pin "2") (pinfunction "2_2") (pintype "passive"))
    )
    (net (code "55") (name "/USER_LED1") (class "Default")
      (node (ref "R11") (pin "1") (pinfunction "1_1") (pintype "passive"))
    )
    (net (code "56") (name "/XIN") (class "Default")
      (node (ref "C20") (pin "2") (pinfunction "2_2") (pintype "passive"))
      (node (ref "U2") (pin "20") (pinfunction "XIN_20") (pintype "input"))
      (node (ref "X1") (pin "2") (pinfunction "2_2") (pintype "passive"))
    )
    (net (code "57") (name "/XOUT") (class "Default")
      (node (ref "R22") (pin "2") (pinfunction "2_2") (pintype "passive"))
      (node (ref "U2") (pin "21") (pinfunction "XOUT_21") (pintype "output"))
    )
    (net (code "58") (name "3.3V") (class "Default")
      (node (ref "C24") (pin "2") (pinfunction "2_2") (pintype "passive"))
      (node (ref "C30") (pin "2") (pinfunction "2_2") (pintype "passive"))
      (node (ref "C39") (pin "2") (pinfunction "2_2") (pintype "passive"))
      (node (ref "R26") (pin "2") (pinfunction "2_2") (pintype "passive"))
      (node (ref "R27") (pin "2") (pinfunction "2_2") (pintype "passive"))
      (node (ref "R30") (pin "2") (pinfunction "2_2") (pintype "passive"))
      (node (ref "R31") (pin "2") (pinfunction "2_2") (pintype "passive"))
      (node (ref "R34") (pin "2") (pinfunction "2_2") (pintype "passive"))
      (node (ref "R35") (pin "2") (pinfunction "2_2") (pintype "passive"))
    )
    (net (code "59") (name "5V_LED") (class "Default")
      (node (ref "C27") (pin "2") (pinfunction "2_2") (pintype "passive"))
      (node (ref "C28") (pin "2") (pinfunction "2_2") (pintype "passive"))
      (node (ref "C29") (pin "2") (pinfunction "2_2") (pintype "passive"))
      (node (ref "C33") (pin "1") (pinfunction "1_1") (pintype "passive"))
      (node (ref "C34") (pin "1") (pinfunction "1_1") (pintype "passive"))
      (node (ref "C35") (pin "1") (pinfunction "1_1") (pintype "passive"))
      (node (ref "C36") (pin "2") (pinfunction "2_2") (pintype "passive"))
      (node (ref "C37") (pin "2") (pinfunction "2_2") (pintype "passive"))
      (node (ref "C38") (pin "2") (pinfunction "2_2") (pintype "passive"))
      (node (ref "D12") (pin "1") (pinfunction "VDD_1") (pintype "power_in"))
      (node (ref "D13") (pin "1") (pinfunction "VDD_1") (pintype "power_in"))
      (node (ref "D14") (pin "1") (pinfunction "VDD_1") (pintype "power_in"))
      (node (ref "D21") (pin "1") (pinfunction "VDD_1") (pintype "power_in"))
      (node (ref "D22") (pin "1") (pinfunction "VDD_1") (pintype "power_in"))
      (node (ref "D23") (pin "1") (pinfunction "VDD_1") (pintype "power_in"))
      (node (ref "D6") (pin "1") (pinfunction "VDD_1") (pintype "power_in"))
      (node (ref "D7") (pin "1") (pinfunction "VDD_1") (pintype "power_in"))
      (node (ref "D8") (pin "1") (pinfunction "VDD_1") (pintype "power_in"))
      (node (ref "R1") (pin "2") (pinfunction "2_2") (pintype "passive"))
    )
    (net (code "60") (name "5V_SYS") (class "Default")
      (node (ref "C4") (pin "2") (pinfunction "2_2") (pintype "passive"))
      (node (ref "R1") (pin "1") (pinfunction "1_1") (pintype "passive"))
      (node (ref "R4") (pin "2") (pinfunction "2_2") (pintype "passive"))
      (node (ref "U") (pin "1") (pinfunction "IN_1") (pintype "power_in"))
      (node (ref "Z1") (pin "2") (pinfunction "K_2") (pintype "passive"))
    )
    (net (code "61") (name "5V_USB") (class "Default")
      (node (ref "C21") (pin "2") (pinfunction "2_2") (pintype "passive"))
      (node (ref "D1") (pin "5") (pinfunction "VBUS_5") (pintype "power_in"))
      (node (ref "J1") (pin "A4B9") (pinfunction "VBUS_A4B9") (pintype "power_in"))
      (node (ref "J1") (pin "B4A9") (pinfunction "VBUS_B4A9") (pintype "power_in"))
      (node (ref "Uled") (pin "14") (pinfunction "VCC_14") (pintype "power_in"))
      (node (ref "Z1") (pin "1") (pinfunction "A_1") (pintype "passive"))
    )
    (net (code "62") (name "GND") (class "Default")
      (node (ref "C1") (pin "1") (pinfunction "1_1") (pintype "passive"))
      (node (ref "C10") (pin "2") (pinfunction "2_2") (pintype "passive"))
      (node (ref "C11") (pin "2") (pinfunction "2_2") (pintype "passive"))
      (node (ref "C12") (pin "2") (pinfunction "2_2") (pintype "passive"))
      (node (ref "C13") (pin "2") (pinfunction "2_2") (pintype "passive"))
      (node (ref "C14") (pin "2") (pinfunction "2_2") (pintype "passive"))
      (node (ref "C15") (pin "1") (pinfunction "1_1") (pintype "passive"))
      (node (ref "C16") (pin "2") (pinfunction "2_2") (pintype "passive"))
      (node (ref "C17") (pin "1") (pinfunction "1_1") (pintype "passive"))
      (node (ref "C2") (pin "1") (pinfunction "1_1") (pintype "passive"))
      (node (ref "C20") (pin "1") (pinfunction "1_1") (pintype "passive"))
      (node (ref "C21") (pin "1") (pinfunction "1_1") (pintype "passive"))
      (node (ref "C22") (pin "1") (pinfunction "1_1") (pintype "passive"))
      (node (ref "C23") (pin "1") (pinfunction "1_1") (pintype "passive"))
      (node (ref "C24") (pin "1") (pinfunction "1_1") (pintype "passive"))
      (node (ref "C25") (pin "1") (pinfunction "1_1") (pintype "passive"))
      (node (ref "C26") (pin "1") (pinfunction "1_1") (pintype "passive"))
      (node (ref "C27") (pin "1") (pinfunction "1_1") (pintype "passive"))
      (node (ref "C28") (pin "1") (pinfunction "1_1") (pintype "passive"))
      (node (ref "C29") (pin "1") (pinfunction "1_1") (pintype "passive"))
      (node (ref "C3") (pin "1") (pinfunction "1_1") (pintype "passive"))
      (node (ref "C30") (pin "1") (pinfunction "1_1") (pintype "passive"))
      (node (ref "C31") (pin "1") (pinfunction "1_1") (pintype "passive"))
      (node (ref "C32") (pin "1") (pinfunction "1_1") (pintype "passive"))
      (node (ref "C33") (pin "2") (pinfunction "2_2") (pintype "passive"))
      (node (ref "C34") (pin "2") (pinfunction "2_2") (pintype "passive"))
      (node (ref "C35") (pin "2") (pinfunction "2_2") (pintype "passive"))
      (node (ref "C36") (pin "1") (pinfunction "1_1") (pintype "passive"))
      (node (ref "C37") (pin "1") (pinfunction "1_1") (pintype "passive"))
      (node (ref "C38") (pin "1") (pinfunction "1_1") (pintype "passive"))
      (node (ref "C39") (pin "1") (pinfunction "1_1") (pintype "passive"))
      (node (ref "C4") (pin "1") (pinfunction "1_1") (pintype "passive"))
      (node (ref "C40") (pin "1") (pinfunction "1_1") (pintype "passive"))
      (node (ref "C41") (pin "1") (pinfunction "1_1") (pintype "passive"))
      (node (ref "C5") (pin "2") (pinfunction "2_2") (pintype "passive"))
      (node (ref "C6") (pin "2") (pinfunction "2_2") (pintype "passive"))
      (node (ref "C7") (pin "2") (pinfunction "2_2") (pintype "passive"))
      (node (ref "C8") (pin "2") (pinfunction "2_2") (pintype "passive"))
      (node (ref "C9") (pin "2") (pinfunction "2_2") (pintype "passive"))
      (node (ref "D1") (pin "2") (pinfunction "GND_2") (pintype "power_in"))
      (node (ref "D12") (pin "3") (pinfunction "GND_3") (pintype "power_in"))
      (node (ref "D13") (pin "3") (pinfunction "GND_3") (pintype "power_in"))
      (node (ref "D14") (pin "3") (pinfunction "GND_3") (pintype "power_in"))
      (node (ref "D21") (pin "3") (pinfunction "GND_3") (pintype "power_in"))
      (node (ref "D22") (pin "3") (pinfunction "GND_3") (pintype "power_in"))
      (node (ref "D23") (pin "3") (pinfunction "GND_3") (pintype "power_in"))
      (node (ref "D6") (pin "3") (pinfunction "GND_3") (pintype "power_in"))
      (node (ref "D7") (pin "3") (pinfunction "GND_3") (pintype "power_in"))
      (node (ref "D8") (pin "3") (pinfunction "GND_3") (pintype "power_in"))
      (node (ref "J1") (pin "A1B12") (pinfunction "GND_A1B12") (pintype "power_in"))
      (node (ref "J1") (pin "B1A12") (pinfunction "GND_B1A12") (pintype "power_in"))
      (node (ref "J1") (pin "SH") (pinfunction "SH_SH") (pintype "power_in"))
      (node (ref "LED2") (pin "2") (pinfunction "K_2") (pintype "passive"))
      (node (ref "R13") (pin "1") (pinfunction "1_1") (pintype "passive"))
      (node (ref "R14") (pin "1") (pinfunction "1_1") (pintype "passive"))
      (node (ref "S1") (pin "C") (pinfunction "COMMON_C") (pintype "passive"))
      (node (ref "S1") (pin "SH1") (pinfunction "SHIELD_SH1") (pintype "passive"))
      (node (ref "S1") (pin "SH2") (pinfunction "SHIELD_SH2") (pintype "passive"))
      (node (ref "S2") (pin "C") (pinfunction "COMMON_C") (pintype "passive"))
      (node (ref "S2") (pin "SH1") (pinfunction "SHIELD_SH1") (pintype "passive"))
      (node (ref "S2") (pin "SH2") (pinfunction "SHIELD_SH2") (pintype "passive"))
      (node (ref "S3") (pin "C") (pinfunction "COMMON_C") (pintype "passive"))
      (node (ref "S3") (pin "SH1") (pinfunction "SHIELD_SH1") (pintype "passive"))
      (node (ref "S3") (pin "SH2") (pinfunction "SHIELD_SH2") (pintype "passive"))
      (node (ref "SW1") (pin "34") (pintype "passive"))
      (node (ref "SW2") (pin "34") (pintype "passive"))
      (node (ref "U") (pin "2") (pinfunction "GND_2") (pintype "power_in"))
      (node (ref "U") (pin "4") (pinfunction "NC_4") (pintype "open_collector"))
      (node (ref "U1") (pin "4") (pinfunction "GND_4") (pintype "power_in"))
      (node (ref "U2") (pin "19") (pinfunction "TESTEN_19") (pintype "input"))
      (node (ref "U2") (pin "57") (pinfunction "EPAD_57") (pintype "power_in"))
      (node (ref "Uled") (pin "3") (pinfunction "GND_3") (pintype "power_in"))
    )
    (net (code "63") (name "Net-(C22-Pad2)") (class "Default")
      (node (ref "C22") (pin "2") (pinfunction "2_2") (pintype "passive"))
      (node (ref "R22") (pin "1") (pinfunction "1_1") (pintype "passive"))
      (node (ref "X1") (pin "1") (pinfunction "1_1") (pintype "passive"))
    )
    (net (code "64") (name "Net-(D3-CB)") (class "Default")
      (node (ref "D3") (pin "3") (pinfunction "CB_3") (pintype "passive"))
      (node (ref "R21") (pin "2") (pinfunction "2_2") (pintype "passive"))
    )
    (net (code "65") (name "Net-(D3-CG)") (class "Default")
      (node (ref "D3") (pin "2") (pinfunction "CG_2") (pintype "passive"))
      (node (ref "R17") (pin "2") (pinfunction "2_2") (pintype "passive"))
    )
    (net (code "66") (name "Net-(D3-CR)") (class "Default")
      (node (ref "D3") (pin "1") (pinfunction "CR_1") (pintype "passive"))
      (node (ref "R15") (pin "2") (pinfunction "2_2") (pintype "passive"))
    )
    (net (code "67") (name "Net-(D6-DOUT)") (class "Default")
      (node (ref "D6") (pin "2") (pinfunction "DOUT_2") (pintype "output"))
      (node (ref "D7") (pin "4") (pinfunction "DIN_4") (pintype "input"))
    )
    (net (code "68") (name "Net-(D7-DOUT)") (class "Default")
      (node (ref "D7") (pin "2") (pinfunction "DOUT_2") (pintype "output"))
      (node (ref "D8") (pin "4") (pinfunction "DIN_4") (pintype "input"))
    )
    (net (code "69") (name "Net-(D12-DIN)") (class "Default")
      (node (ref "D12") (pin "4") (pinfunction "DIN_4") (pintype "input"))
      (node (ref "D8") (pin "2") (pinfunction "DOUT_2") (pintype "output"))
    )
    (net (code "70") (name "Net-(D12-DOUT)") (class "Default")
      (node (ref "D12") (pin "2") (pinfunction "DOUT_2") (pintype "output"))
      (node (ref "D13") (pin "4") (pinfunction "DIN_4") (pintype "input"))
    )
    (net (code "71") (name "Net-(D13-DOUT)") (class "Default")
      (node (ref "D13") (pin "2") (pinfunction "DOUT_2") (pintype "output"))
      (node (ref "D14") (pin "4") (pinfunction "DIN_4") (pintype "input"))
    )
    (net (code "72") (name "Net-(D14-DOUT)") (class "Default")
      (node (ref "D14") (pin "2") (pinfunction "DOUT_2") (pintype "output"))
      (node (ref "D21") (pin "4") (pinfunction "DIN_4") (pintype "input"))
    )
    (net (code "73") (name "Net-(D21-DOUT)") (class "Default")
      (node (ref "D21") (pin "2") (pinfunction "DOUT_2") (pintype "output"))
      (node (ref "D22") (pin "4") (pinfunction "DIN_4") (pintype "input"))
    )
    (net (code "74") (name "Net-(D22-DOUT)") (class "Default")
      (node (ref "D22") (pin "2") (pinfunction "DOUT_2") (pintype "output"))
      (node (ref "D23") (pin "4") (pinfunction "DIN_4") (pintype "input"))
    )
    (net (code "75") (name "Net-(J1-CC1)") (class "Default")
      (node (ref "J1") (pin "A5") (pinfunction "CC1_A5") (pintype "passive"))
      (node (ref "R14") (pin "2") (pinfunction "2_2") (pintype "passive"))
    )
    (net (code "76") (name "Net-(J1-CC2)") (class "Default")
      (node (ref "J1") (pin "B5") (pinfunction "CC2_B5") (pintype "tri_state"))
      (node (ref "R13") (pin "2") (pinfunction "2_2") (pintype "passive"))
    )
    (net (code "77") (name "Net-(J1-DN1)") (class "Default")
      (node (ref "D1") (pin "1") (pinfunction "IO1_1") (pintype "bidirectional"))
      (node (ref "J1") (pin "A7") (pinfunction "DN1_A7") (pintype "bidirectional"))
      (node (ref "J1") (pin "B7") (pinfunction "DN2_B7") (pintype "bidirectional"))
    )
    (net (code "78") (name "Net-(J1-DP1)") (class "Default")
      (node (ref "D1") (pin "3") (pinfunction "IO2_3") (pintype "bidirectional"))
      (node (ref "J1") (pin "A6") (pinfunction "DP1_A6") (pintype "bidirectional"))
      (node (ref "J1") (pin "B6") (pinfunction "DP2_B6") (pintype "bidirectional"))
    )
    (net (code "79") (name "Net-(J2-S)") (class "Default")
      (node (ref "D2") (pin "A") (pinfunction "A_A") (pintype "passive"))
      (node (ref "J2") (pin "P$2") (pinfunction "S_P$2") (pintype "passive"))
    )
    (net (code "80") (name "Net-(J3-S)") (class "Default")
      (node (ref "D4") (pin "A") (pinfunction "A_A") (pintype "passive"))
      (node (ref "J3") (pin "P$2") (pinfunction "S_P$2") (pintype "passive"))
    )
    (net (code "81") (name "Net-(J4-S)") (class "Default")
      (node (ref "D5") (pin "A") (pinfunction "A_A") (pintype "passive"))
      (node (ref "J4") (pin "P$2") (pinfunction "S_P$2") (pintype "passive"))
    )
    (net (code "82") (name "Net-(J5-S)") (class "Default")
      (node (ref "D9") (pin "A") (pinfunction "A_A") (pintype "passive"))
      (node (ref "J5") (pin "P$2") (pinfunction "S_P$2") (pintype "passive"))
    )
    (net (code "83") (name "Net-(J6-S)") (class "Default")
      (node (ref "D10") (pin "A") (pinfunction "A_A") (pintype "passive"))
      (node (ref "J6") (pin "P$2") (pinfunction "S_P$2") (pintype "passive"))
    )
    (net (code "84") (name "Net-(J7-S)") (class "Default")
      (node (ref "D11") (pin "A") (pinfunction "A_A") (pintype "passive"))
      (node (ref "J7") (pin "P$2") (pinfunction "S_P$2") (pintype "passive"))
    )
    (net (code "85") (name "Net-(J8-S)") (class "Default")
      (node (ref "D15") (pin "A") (pinfunction "A_A") (pintype "passive"))
      (node (ref "J8") (pin "P$2") (pinfunction "S_P$2") (pintype "passive"))
    )
    (net (code "86") (name "Net-(J9-S)") (class "Default")
      (node (ref "D16") (pin "A") (pinfunction "A_A") (pintype "passive"))
      (node (ref "J9") (pin "P$2") (pinfunction "S_P$2") (pintype "passive"))
    )
    (net (code "87") (name "Net-(J10-S)") (class "Default")
      (node (ref "D17") (pin "A") (pinfunction "A_A") (pintype "passive"))
      (node (ref "J10") (pin "P$2") (pinfunction "S_P$2") (pintype "passive"))
    )
    (net (code "88") (name "Net-(LED2-A)") (class "Default")
      (node (ref "LED2") (pin "1") (pinfunction "A_1") (pintype "passive"))
      (node (ref "R11") (pin "2") (pinfunction "2_2") (pintype "passive"))
    )
    (net (code "89") (name "Net-(R5-Pad2)") (class "Default")
      (node (ref "R5") (pin "2") (pinfunction "2_2") (pintype "passive"))
      (node (ref "SW1") (pin "12") (pintype "passive"))
    )
    (net (code "90") (name "Net-(S1-CHANNEL_A)") (class "Default")
      (node (ref "R26") (pin "1") (pinfunction "1_1") (pintype "passive"))
      (node (ref "R28") (pin "1") (pinfunction "1_1") (pintype "passive"))
      (node (ref "S1") (pin "A") (pinfunction "CHANNEL_A_A") (pintype "passive"))
    )
    (net (code "91") (name "Net-(S1-CHANNEL_B)") (class "Default")
      (node (ref "R27") (pin "1") (pinfunction "1_1") (pintype "passive"))
      (node (ref "R29") (pin "1") (pinfunction "1_1") (pintype "passive"))
      (node (ref "S1") (pin "B") (pinfunction "CHANNEL_B_B") (pintype "passive"))
    )
    (net (code "92") (name "Net-(S2-CHANNEL_A)") (class "Default")
      (node (ref "R30") (pin "1") (pinfunction "1_1") (pintype "passive"))
      (node (ref "R32") (pin "1") (pinfunction "1_1") (pintype "passive"))
      (node (ref "S2") (pin "A") (pinfunction "CHANNEL_A_A") (pintype "passive"))
    )
    (net (code "93") (name "Net-(S2-CHANNEL_B)") (class "Default")
      (node (ref "R31") (pin "1") (pinfunction "1_1") (pintype "passive"))
      (node (ref "R33") (pin "1") (pinfunction "1_1") (pintype "passive"))
      (node (ref "S2") (pin "B") (pinfunction "CHANNEL_B_B") (pintype "passive"))
    )
    (net (code "94") (name "Net-(S3-CHANNEL_A)") (class "Default")
      (node (ref "R34") (pin "1") (pinfunction "1_1") (pintype "passive"))
      (node (ref "R36") (pin "1") (pinfunction "1_1") (pintype "passive"))
      (node (ref "S3") (pin "A") (pinfunction "CHANNEL_A_A") (pintype "passive"))
    )
    (net (code "95") (name "Net-(S3-CHANNEL_B)") (class "Default")
      (node (ref "R35") (pin "1") (pinfunction "1_1") (pintype "passive"))
      (node (ref "R37") (pin "1") (pinfunction "1_1") (pintype "passive"))
      (node (ref "S3") (pin "B") (pinfunction "CHANNEL_B_B") (pintype "passive"))
    )
    (net (code "96") (name "Net-(U-EN)") (class "Default")
      (node (ref "R4") (pin "1") (pinfunction "1_1") (pintype "passive"))
      (node (ref "U") (pin "3") (pinfunction "EN_3") (pintype "input"))
    )
    (net (code "97") (name "Net-(U2-USB_DM)") (class "Default")
      (node (ref "R7") (pin "1") (pinfunction "1_1") (pintype "passive"))
      (node (ref "U2") (pin "46") (pinfunction "USB_DM_46") (pintype "bidirectional"))
    )
    (net (code "98") (name "Net-(U2-USB_DP)") (class "Default")
      (node (ref "R6") (pin "1") (pinfunction "1_1") (pintype "passive"))
      (node (ref "U2") (pin "47") (pinfunction "USB_DP_47") (pintype "bidirectional"))
    )
    (net (code "99") (name "Net-(Uled-A)") (class "Default")
      (node (ref "R24") (pin "2") (pinfunction "2_2") (pintype "passive"))
      (node (ref "Uled") (pin "1") (pinfunction "NC_1") (pintype "power_in"))
      (node (ref "Uled") (pin "2") (pinfunction "A_2") (pintype "passive"))
    )
    (net (code "100") (name "unconnected-(D23-DOUT-Pad2)") (class "Default")
      (node (ref "D23") (pin "2") (pinfunction "DOUT_2") (pintype "output"))
    )
    (net (code "101") (name "unconnected-(J1-SBU1-PadA8)") (class "Default")
      (node (ref "J1") (pin "A8") (pinfunction "SBU1_A8") (pintype "bidirectional"))
    )
    (net (code "102") (name "unconnected-(J1-SBU2-PadB8)") (class "Default")
      (node (ref "J1") (pin "B8") (pinfunction "SBU2_B8") (pintype "bidirectional"))
    )
    (net (code "103") (name "unconnected-(U2-GPIO29_ADC3-Pad41)") (class "Default")
      (node (ref "U2") (pin "41") (pinfunction "GPIO29_ADC3_41") (pintype "bidirectional"))
    )
  )
)
